# Land_Traffic_Controller.net
KiCad netlist of a schematic drawn in EasyEDA
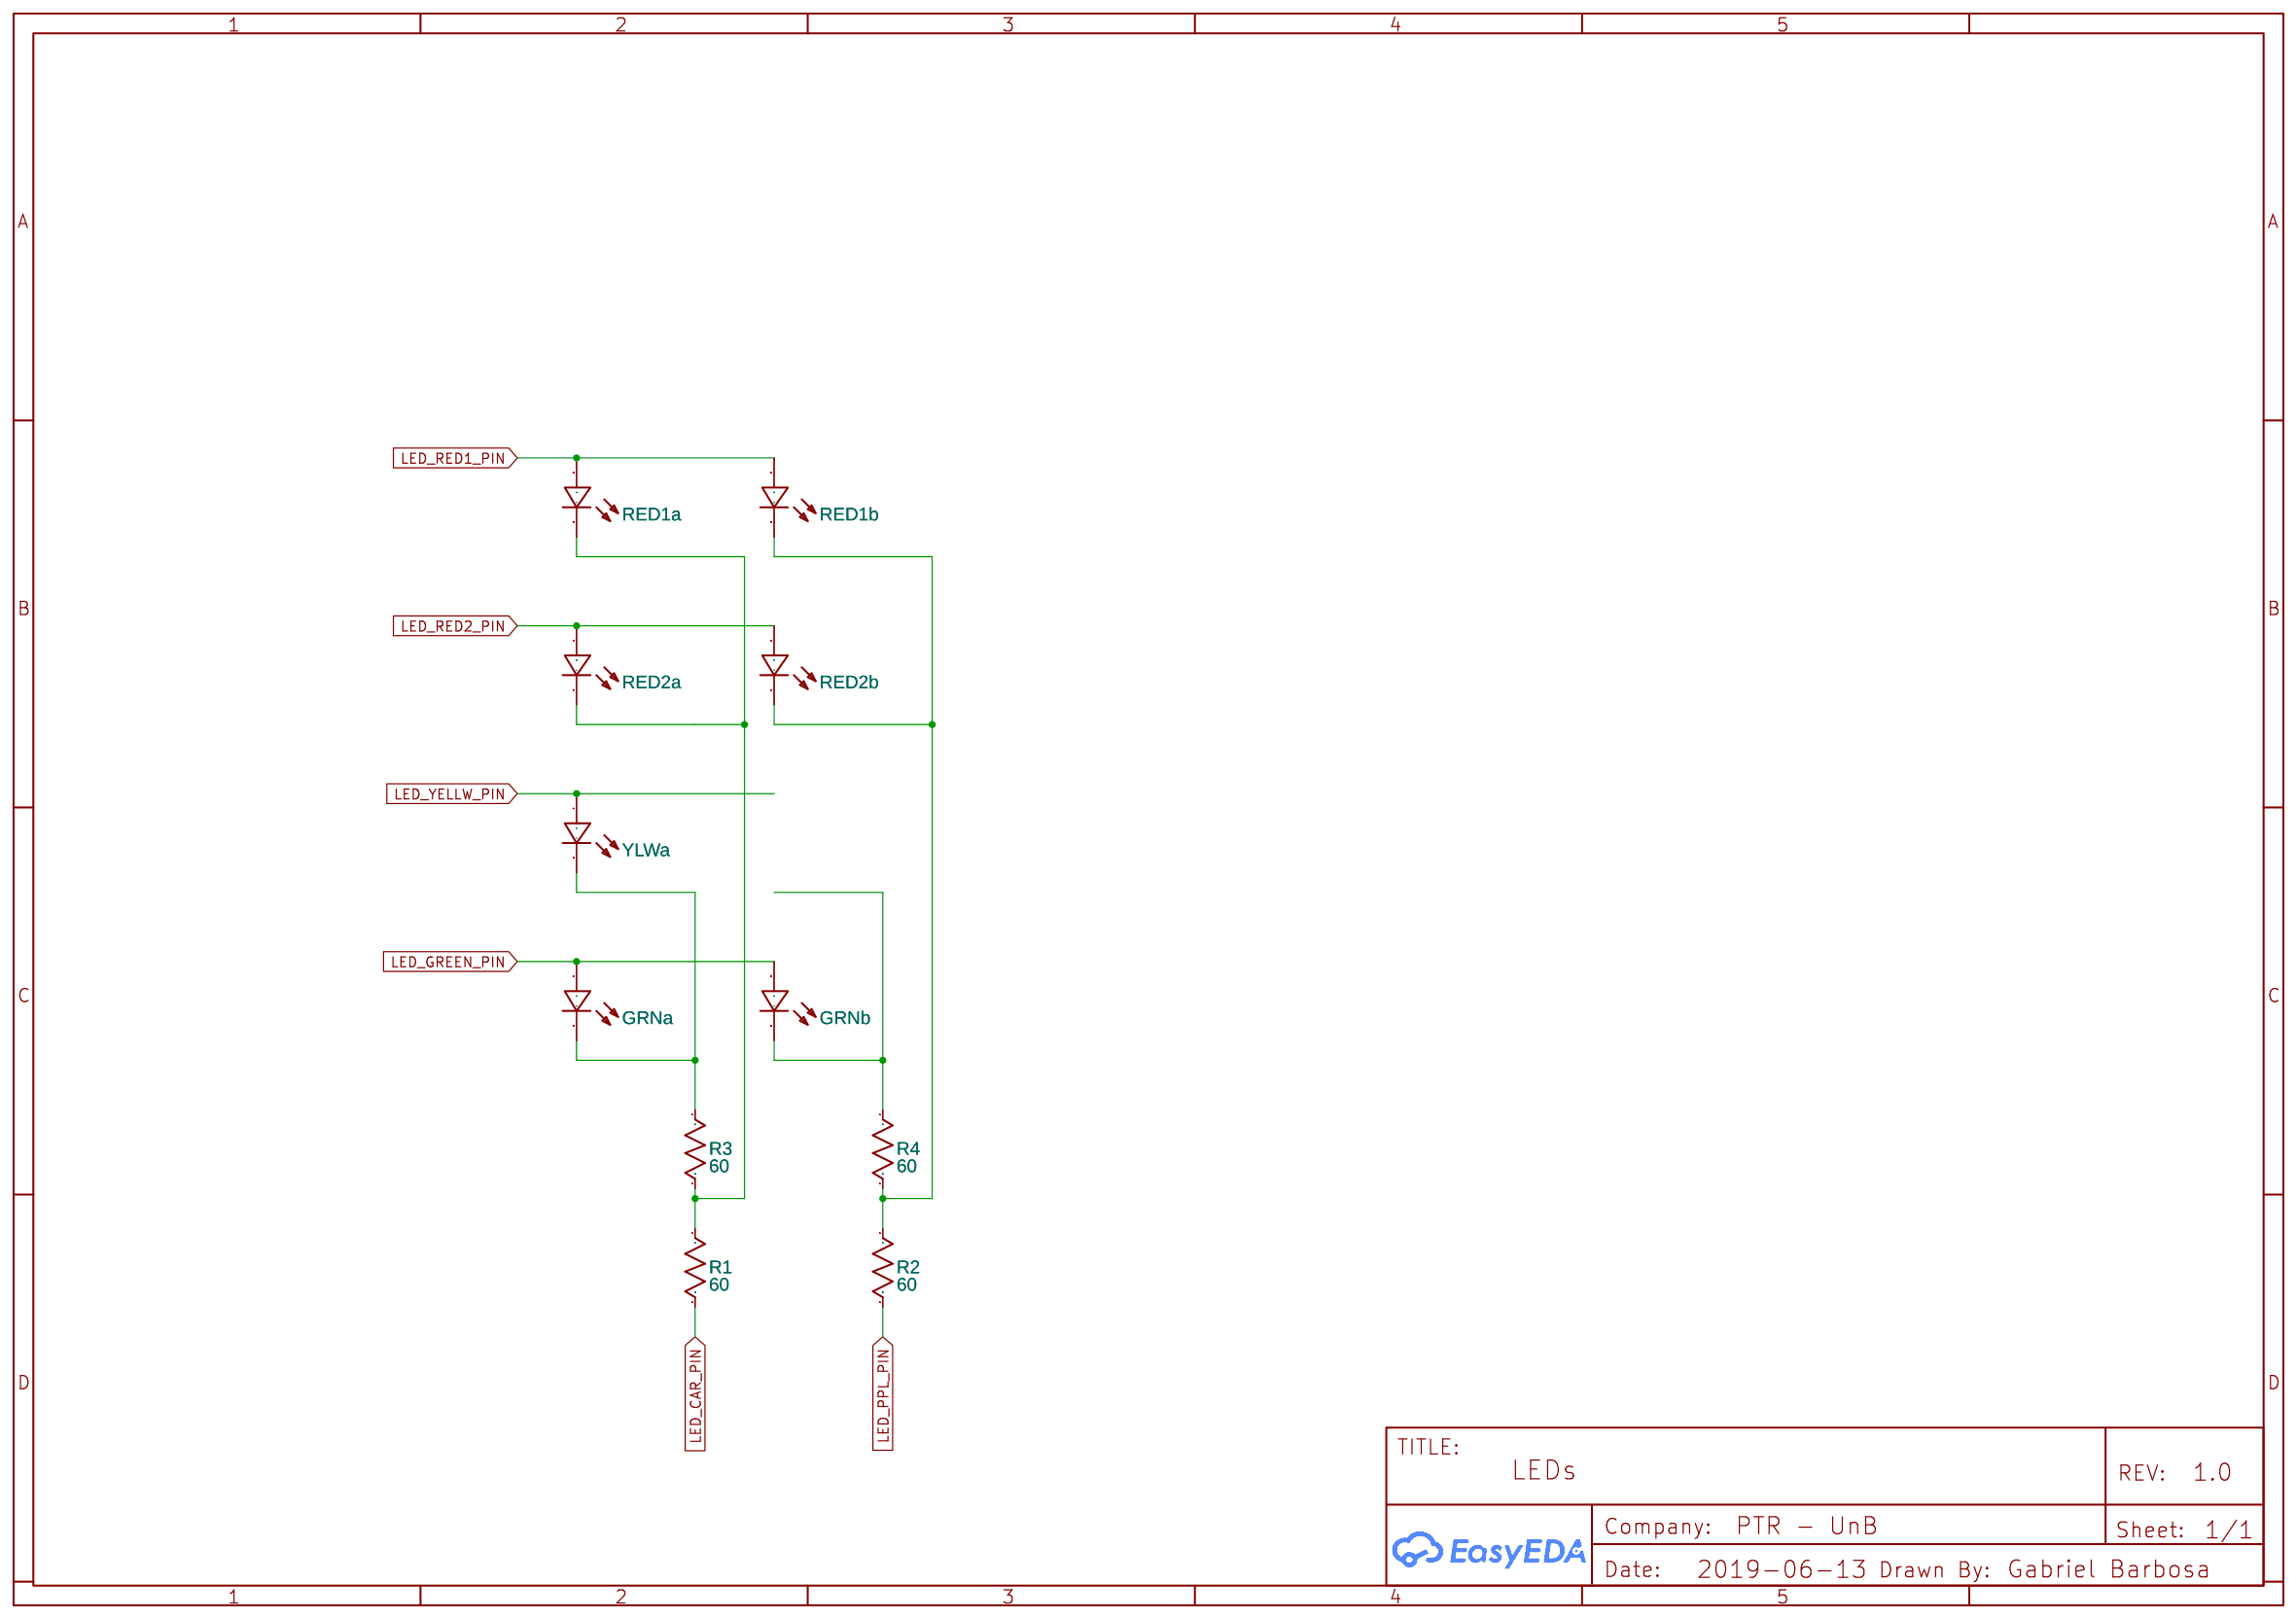
[diagram p0: LEDs]
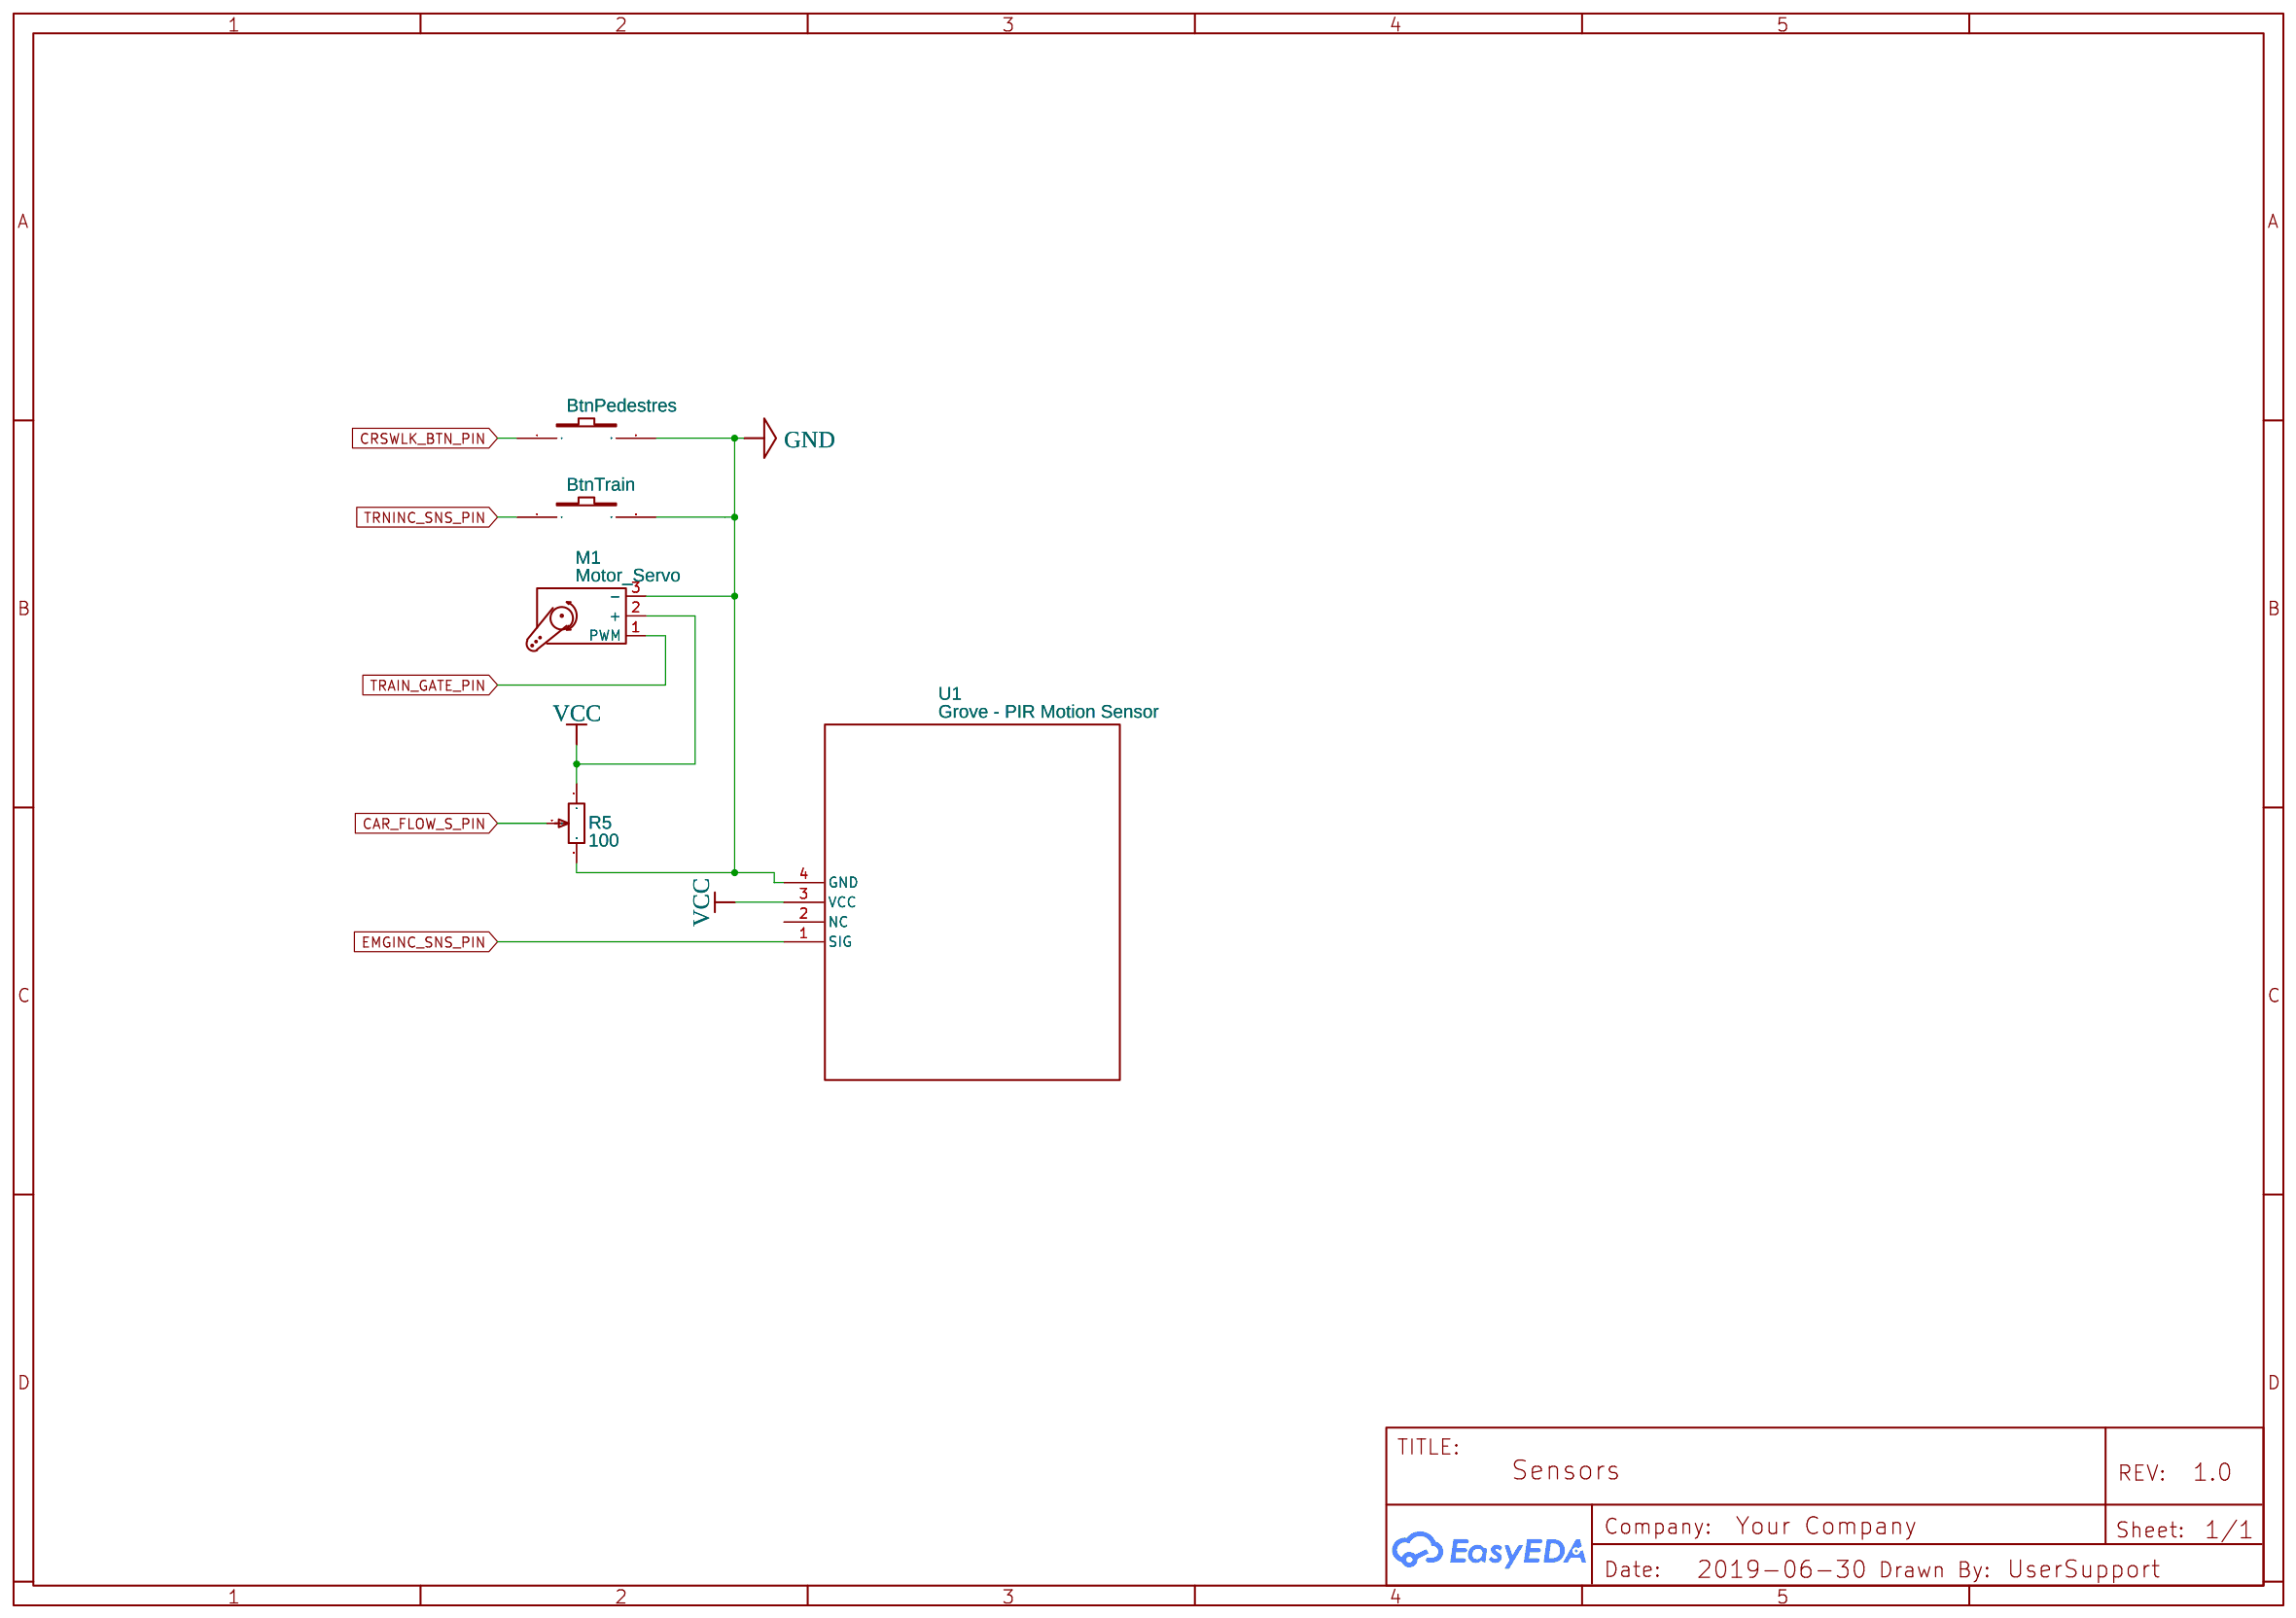
[diagram p1: Sensors]

(export (version "E")
  (design (tool "Eeschema 10.0.6"))
  (components
    (comp (ref "LED1")
      (value "RED1a")
      (fields
        (field (name "BOM_Manufacturer Part") "204-10SURD/S530-A3")
        (field (name "BOM_Supplier Part") "C99772")
      )
      (libsource (lib "") (part "Unknown_290_245"))
    )
    (comp (ref "LED2")
      (value "RED1b")
      (fields
        (field (name "BOM_Manufacturer Part") "204-10SURD/S530-A3")
        (field (name "BOM_Supplier Part") "C99772")
      )
      (libsource (lib "") (part "Unknown_390_245"))
    )
    (comp (ref "LED3")
      (value "RED2a")
      (fields
        (field (name "BOM_Manufacturer Part") "204-10SURD/S530-A3")
        (field (name "BOM_Supplier Part") "C99772")
      )
      (libsource (lib "") (part "Unknown_290_330"))
    )
    (comp (ref "LED4")
      (value "RED2b")
      (fields
        (field (name "BOM_Manufacturer Part") "204-10SURD/S530-A3")
        (field (name "BOM_Supplier Part") "C99772")
      )
      (libsource (lib "") (part "Unknown_390_330"))
    )
    (comp (ref "LED5")
      (value "YLWa")
      (fields
        (field (name "BOM_Manufacturer Part") "204-10SURD/S530-A3")
        (field (name "BOM_Supplier Part") "C99772")
      )
      (libsource (lib "") (part "Unknown_290_415"))
    )
    (comp (ref "LED7")
      (value "GRNa")
      (fields
        (field (name "BOM_Manufacturer Part") "204-10SURD/S530-A3")
        (field (name "BOM_Supplier Part") "C99772")
      )
      (libsource (lib "") (part "Unknown_290_500"))
    )
    (comp (ref "LED8")
      (value "GRNb")
      (fields
        (field (name "BOM_Manufacturer Part") "204-10SURD/S530-A3")
        (field (name "BOM_Supplier Part") "C99772")
      )
      (libsource (lib "") (part "Unknown_390_500"))
    )
    (comp (ref "R1")
      (value "60")
      (fields (field (name "BOM_Manufacturer Part") "?"))
      (libsource (lib "") (part "Res_AXIAL-0.3(1/8W)_US"))
    )
    (comp (ref "R2")
      (value "60")
      (fields (field (name "BOM_Manufacturer Part") "?"))
      (libsource (lib "") (part "Res_AXIAL-0.3(1/8W)_US"))
    )
    (comp (ref "R3")
      (value "60")
      (fields (field (name "BOM_Manufacturer Part") "?"))
      (libsource (lib "") (part "Res_AXIAL-0.3(1/8W)_US"))
    )
    (comp (ref "R4")
      (value "60")
      (fields (field (name "BOM_Manufacturer Part") "?"))
      (libsource (lib "") (part "Res_AXIAL-0.3(1/8W)_US"))
    )
    (comp (ref "M1")
      (value "Motor_Servo")
      (fields (field (name "BOM_Manufacturer Part") "?"))
      (libsource (lib "") (part "Unknown_290_305"))
    )
    (comp (ref "R5")
      (value "100")
      (fields
        (field (name "BOM_Manufacturer Part") "3386P-1-101LF")
        (field (name "BOM_Supplier Part") "C125022")
      )
      (libsource (lib "") (part "3386P-1-101LF"))
    )
    (comp (ref "SW1")
      (value "BtnPedestres")
      (fields (field (name "BOM_Manufacturer Part") "EVQ22705R") (field (name "BOM_Supplier Part") "C79156"))
      (libsource (lib "") (part "Unknown_290_215"))
    )
    (comp (ref "SW2")
      (value "BtnTrain")
      (fields (field (name "BOM_Manufacturer Part") "EVQ22705R") (field (name "BOM_Supplier Part") "C79156"))
      (libsource (lib "") (part "Unknown_290_255"))
    )
    (comp (ref "U1")
      (value "Grove - PIR Motion Sensor")
      (fields (field (name "BOM_Manufacturer Part") "?") (field (name "BOM_Supplier Part") "undefined"))
      (libsource (lib "") (part "Unknown_475_450"))
    )
  )
  (nets
    (net (code "1") (name "CAR_FLOW_S_PIN") (class "Default")
      (node (ref "R5") (pin "2") (pinfunction "2_2") (pintype "input"))
    )
    (net (code "2") (name "CRSWLK_BTN_PIN") (class "Default")
      (node (ref "SW1") (pin "1") (pinfunction "1_1") (pintype "input"))
    )
    (net (code "3") (name "EMGINC_SNS_PIN") (class "Default")
      (node (ref "U1") (pin "1") (pinfunction "SIG_1") (pintype "unspecified"))
    )
    (net (code "4") (name "GND") (class "Default")
      (node (ref "M1") (pin "3") (pinfunction "-_3") (pintype "unspecified"))
      (node (ref "R5") (pin "3") (pinfunction "3_3") (pintype "input"))
      (node (ref "SW1") (pin "2") (pinfunction "2_2") (pintype "input"))
      (node (ref "SW2") (pin "2") (pinfunction "2_2") (pintype "input"))
      (node (ref "U1") (pin "4") (pinfunction "GND_4") (pintype "unspecified"))
    )
    (net (code "5") (name "LED_CAR_PIN") (class "Default")
      (node (ref "R1") (pin "2") (pinfunction "2_2") (pintype "unspecified"))
    )
    (net (code "6") (name "LED_GREEN_PIN") (class "Default")
      (node (ref "LED7") (pin "1") (pinfunction "+_1") (pintype "unspecified"))
      (node (ref "LED8") (pin "1") (pinfunction "+_1") (pintype "unspecified"))
    )
    (net (code "7") (name "LED_PPL_PIN") (class "Default")
      (node (ref "R2") (pin "2") (pinfunction "2_2") (pintype "unspecified"))
    )
    (net (code "8") (name "LED_RED1_PIN") (class "Default")
      (node (ref "LED1") (pin "1") (pinfunction "+_1") (pintype "unspecified"))
      (node (ref "LED2") (pin "1") (pinfunction "+_1") (pintype "unspecified"))
    )
    (net (code "9") (name "LED_RED2_PIN") (class "Default")
      (node (ref "LED3") (pin "1") (pinfunction "+_1") (pintype "unspecified"))
      (node (ref "LED4") (pin "1") (pinfunction "+_1") (pintype "unspecified"))
    )
    (net (code "10") (name "LED_YELLW_PIN") (class "Default")
      (node (ref "LED5") (pin "1") (pinfunction "+_1") (pintype "unspecified"))
    )
    (net (code "11") (name "Net-(LED1--)") (class "Default")
      (node (ref "LED1") (pin "2") (pinfunction "-_2") (pintype "unspecified"))
      (node (ref "LED3") (pin "2") (pinfunction "-_2") (pintype "unspecified"))
      (node (ref "R1") (pin "1") (pinfunction "1_1") (pintype "unspecified"))
      (node (ref "R3") (pin "2") (pinfunction "2_2") (pintype "unspecified"))
    )
    (net (code "12") (name "Net-(LED2--)") (class "Default")
      (node (ref "LED2") (pin "2") (pinfunction "-_2") (pintype "unspecified"))
      (node (ref "LED4") (pin "2") (pinfunction "-_2") (pintype "unspecified"))
      (node (ref "R2") (pin "1") (pinfunction "1_1") (pintype "unspecified"))
      (node (ref "R4") (pin "2") (pinfunction "2_2") (pintype "unspecified"))
    )
    (net (code "13") (name "Net-(LED5--)") (class "Default")
      (node (ref "LED5") (pin "2") (pinfunction "-_2") (pintype "unspecified"))
      (node (ref "LED7") (pin "2") (pinfunction "-_2") (pintype "unspecified"))
      (node (ref "R3") (pin "1") (pinfunction "1_1") (pintype "unspecified"))
    )
    (net (code "14") (name "Net-(LED8--)") (class "Default")
      (node (ref "LED8") (pin "2") (pinfunction "-_2") (pintype "unspecified"))
      (node (ref "R4") (pin "1") (pinfunction "1_1") (pintype "unspecified"))
    )
    (net (code "15") (name "TRAIN_GATE_PIN") (class "Default")
      (node (ref "M1") (pin "1") (pinfunction "PWM_1") (pintype "unspecified"))
    )
    (net (code "16") (name "TRNINC_SNS_PIN") (class "Default")
      (node (ref "SW2") (pin "1") (pinfunction "1_1") (pintype "input"))
    )
    (net (code "17") (name "VCC") (class "Default")
      (node (ref "M1") (pin "2") (pinfunction "+_2") (pintype "unspecified"))
      (node (ref "R5") (pin "1") (pinfunction "1_1") (pintype "input"))
      (node (ref "U1") (pin "3") (pinfunction "VCC_3") (pintype "unspecified"))
    )
    (net (code "18") (name "unconnected-(U1-NC-Pad2)") (class "Default")
      (node (ref "U1") (pin "2") (pinfunction "NC_2") (pintype "unspecified"))
    )
  )
)
